# source_wifi_rev_a.net
KiCad netlist of a schematic drawn in EAGLE
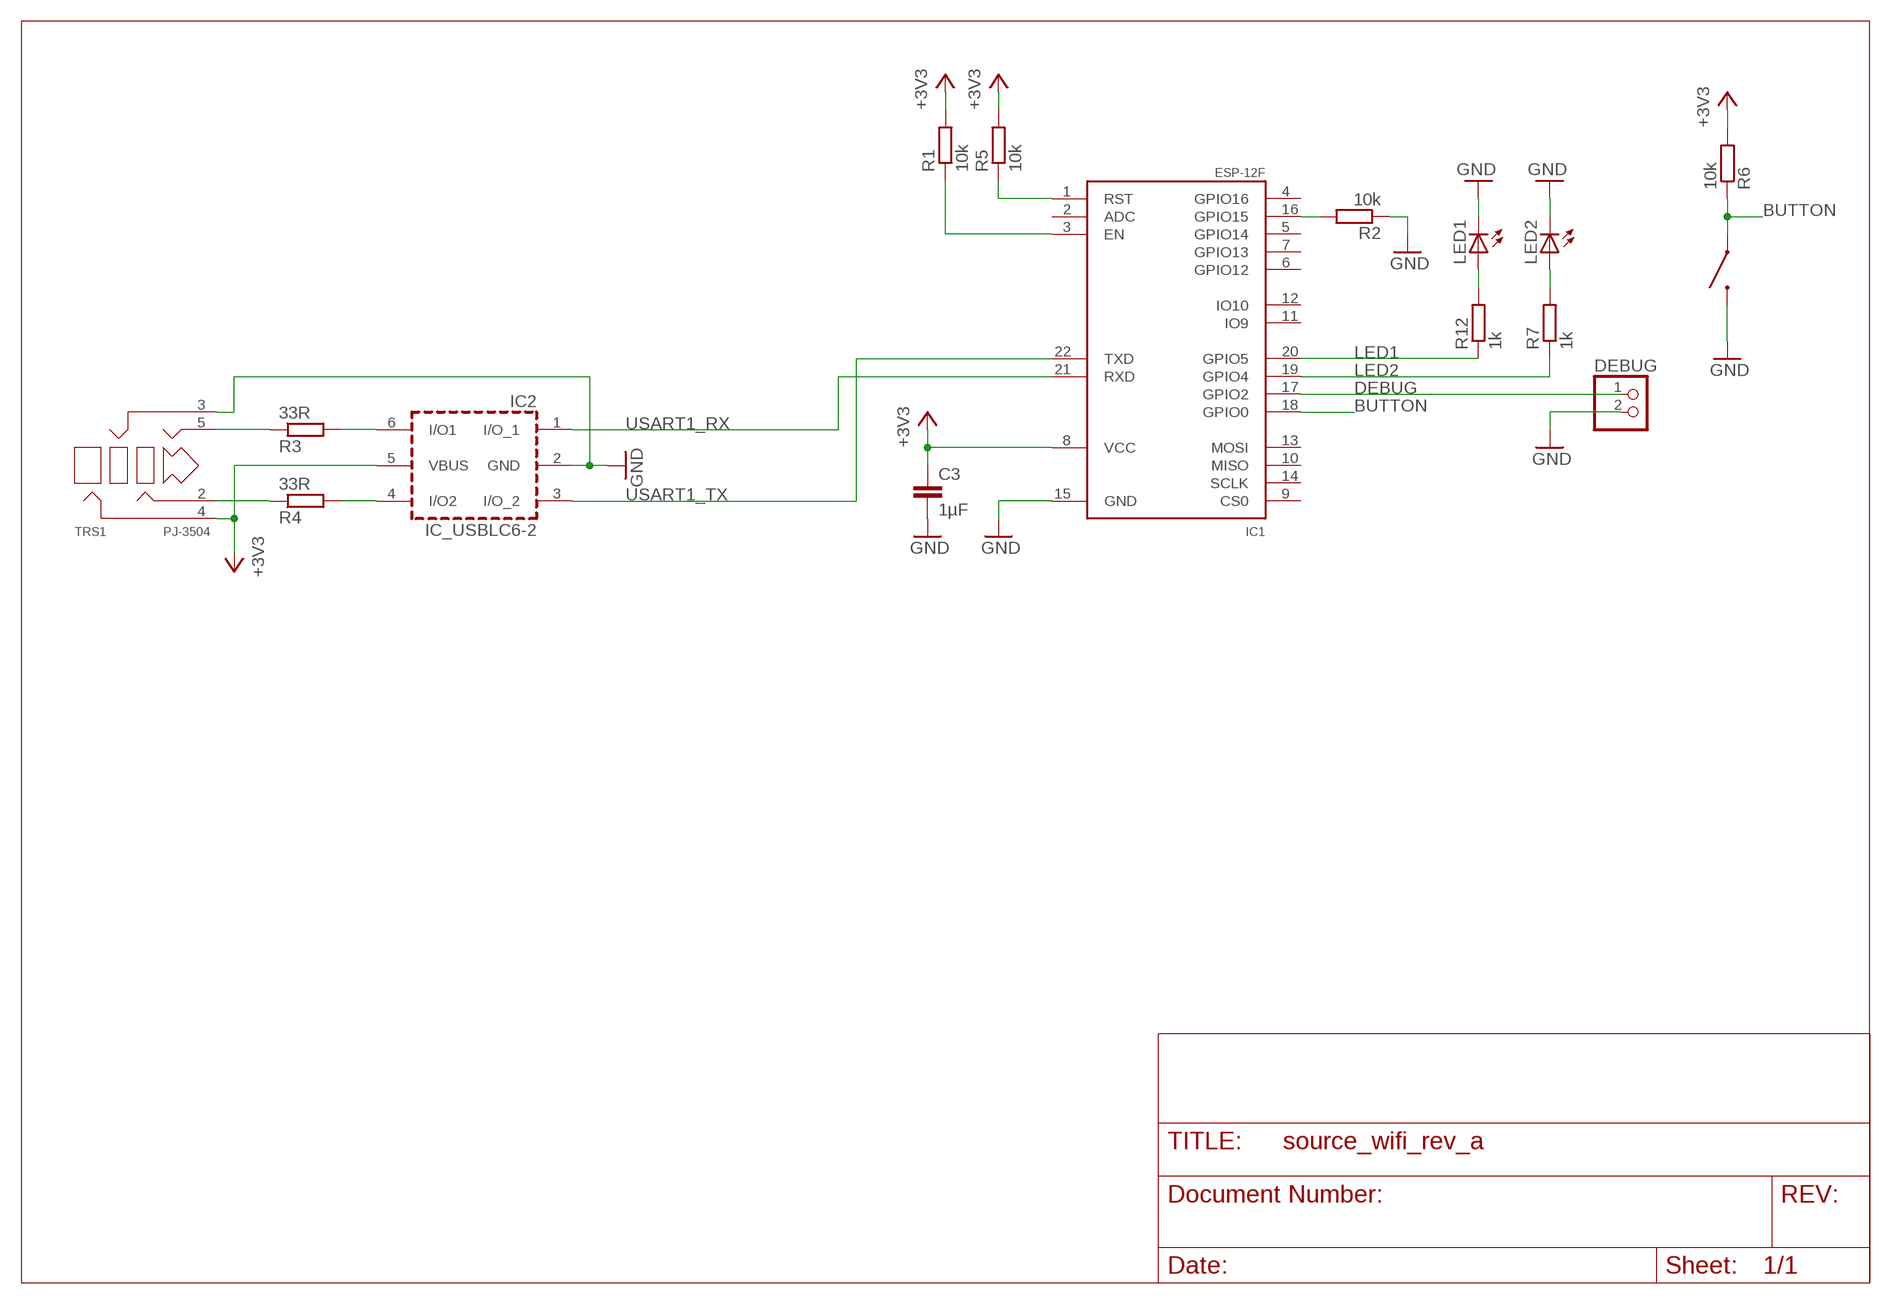
[diagram p0: schematic, sheet 1]

(export (version "E")
  (design (tool "Eeschema 10.0.6"))
  (components
    (comp (ref "C3")
      (value "1µF")
      (footprint "eagle-import:C0603")
      (libsource (lib "eagle-import") (part "C-EUC0603"))
    )
    (comp (ref "DEBUG")
      (value "HEADER-1X2ROUND")
      (footprint "eagle-import:1X02_ROUND")
      (libsource (lib "eagle-import") (part "HEADER-1X2ROUND"))
    )
    (comp (ref "IC1")
      (value "ESP-12F")
      (footprint "eagle-import:ESP-12F")
      (libsource (lib "eagle-import") (part "ESP-12F"))
    )
    (comp (ref "IC2")
      (value "IC_USBLC6-2")
      (footprint "eagle-import:SOT-23-6L")
      (libsource (lib "eagle-import") (part "IC_USBLC6-2"))
    )
    (comp (ref "ISP")
      (value "TACT-SWITCH-40-40")
      (footprint "eagle-import:40-40")
      (libsource (lib "eagle-import") (part "TACT-SWITCH-40-40"))
    )
    (comp (ref "LED1")
      (value "LEDCHIP-LED0603")
      (footprint "eagle-import:CHIP-LED0603")
      (libsource (lib "eagle-import") (part "LEDCHIP-LED0603"))
    )
    (comp (ref "LED2")
      (value "LEDCHIP-LED0603")
      (footprint "eagle-import:CHIP-LED0603")
      (libsource (lib "eagle-import") (part "LEDCHIP-LED0603"))
    )
    (comp (ref "R1")
      (value "10k")
      (footprint "eagle-import:R0603")
      (libsource (lib "eagle-import") (part "R-EU_R0603"))
    )
    (comp (ref "R2")
      (value "10k")
      (footprint "eagle-import:R0603")
      (libsource (lib "eagle-import") (part "R-EU_R0603"))
    )
    (comp (ref "R3")
      (value "33R")
      (footprint "eagle-import:R0603")
      (libsource (lib "eagle-import") (part "R-EU_R0603"))
    )
    (comp (ref "R4")
      (value "33R")
      (footprint "eagle-import:R0603")
      (libsource (lib "eagle-import") (part "R-EU_R0603"))
    )
    (comp (ref "R5")
      (value "10k")
      (footprint "eagle-import:R0603")
      (libsource (lib "eagle-import") (part "R-EU_R0603"))
    )
    (comp (ref "R6")
      (value "10k")
      (footprint "eagle-import:R0603")
      (libsource (lib "eagle-import") (part "R-EU_R0603"))
    )
    (comp (ref "R7")
      (value "1k")
      (footprint "eagle-import:R0603")
      (libsource (lib "eagle-import") (part "R-EU_R0603"))
    )
    (comp (ref "R12")
      (value "1k")
      (footprint "eagle-import:R0603")
      (libsource (lib "eagle-import") (part "R-EU_R0603"))
    )
    (comp (ref "TRS1")
      (value "PJ-3504")
      (footprint "eagle-import:YD-PJ-3504")
      (libsource (lib "eagle-import") (part "PJ-3504"))
    )
  )
  (nets
    (net (code "1") (name "+3V3") (class "Default")
      (node (ref "C3") (pin "1") (pinfunction "1_1") (pintype "passive"))
      (node (ref "IC1") (pin "8") (pinfunction "VCC_8") (pintype "bidirectional"))
      (node (ref "IC2") (pin "5") (pinfunction "VBUS_5") (pintype "bidirectional"))
      (node (ref "R1") (pin "2") (pinfunction "2_2") (pintype "passive"))
      (node (ref "R5") (pin "2") (pinfunction "2_2") (pintype "passive"))
      (node (ref "R6") (pin "2") (pinfunction "2_2") (pintype "passive"))
      (node (ref "TRS1") (pin "4") (pinfunction "4_4") (pintype "bidirectional"))
    )
    (net (code "2") (name "/BUTTON") (class "Default")
      (node (ref "IC1") (pin "18") (pinfunction "GPIO0_18") (pintype "bidirectional"))
      (node (ref "ISP") (pin "3") (pinfunction "P$2_3") (pintype "bidirectional"))
      (node (ref "ISP") (pin "4") (pinfunction "P$2_4") (pintype "bidirectional"))
      (node (ref "R6") (pin "1") (pinfunction "1_1") (pintype "passive"))
    )
    (net (code "3") (name "/DEBUG") (class "Default")
      (node (ref "DEBUG") (pin "1") (pinfunction "1_1") (pintype "passive"))
      (node (ref "IC1") (pin "17") (pinfunction "GPIO2_17") (pintype "bidirectional"))
    )
    (net (code "4") (name "/LED1") (class "Default")
      (node (ref "IC1") (pin "20") (pinfunction "GPIO5_20") (pintype "bidirectional"))
      (node (ref "R12") (pin "1") (pinfunction "1_1") (pintype "passive"))
    )
    (net (code "5") (name "/LED2") (class "Default")
      (node (ref "IC1") (pin "19") (pinfunction "GPIO4_19") (pintype "bidirectional"))
      (node (ref "R7") (pin "1") (pinfunction "1_1") (pintype "passive"))
    )
    (net (code "6") (name "/USART1_RX") (class "Default")
      (node (ref "IC1") (pin "21") (pinfunction "RXD_21") (pintype "bidirectional"))
      (node (ref "IC2") (pin "1") (pinfunction "I/O_1_1") (pintype "bidirectional"))
    )
    (net (code "7") (name "/USART1_TX") (class "Default")
      (node (ref "IC1") (pin "22") (pinfunction "TXD_22") (pintype "bidirectional"))
      (node (ref "IC2") (pin "3") (pinfunction "I/O_2_3") (pintype "bidirectional"))
    )
    (net (code "8") (name "GND") (class "Default")
      (node (ref "C3") (pin "2") (pinfunction "2_2") (pintype "passive"))
      (node (ref "DEBUG") (pin "2") (pinfunction "2_2") (pintype "passive"))
      (node (ref "IC1") (pin "15") (pinfunction "GND_15") (pintype "bidirectional"))
      (node (ref "IC2") (pin "2") (pinfunction "GND_2") (pintype "bidirectional"))
      (node (ref "ISP") (pin "1") (pinfunction "P$1_1") (pintype "bidirectional"))
      (node (ref "ISP") (pin "2") (pinfunction "P$1_2") (pintype "bidirectional"))
      (node (ref "LED1") (pin "C") (pinfunction "C_C") (pintype "passive"))
      (node (ref "LED2") (pin "C") (pinfunction "C_C") (pintype "passive"))
      (node (ref "R2") (pin "1") (pinfunction "1_1") (pintype "passive"))
      (node (ref "TRS1") (pin "3") (pinfunction "3_3") (pintype "bidirectional"))
    )
    (net (code "9") (name "Net-(IC1-EN)") (class "Default")
      (node (ref "IC1") (pin "3") (pinfunction "EN_3") (pintype "bidirectional"))
      (node (ref "R1") (pin "1") (pinfunction "1_1") (pintype "passive"))
    )
    (net (code "10") (name "Net-(IC1-GPIO15)") (class "Default")
      (node (ref "IC1") (pin "16") (pinfunction "GPIO15_16") (pintype "bidirectional"))
      (node (ref "R2") (pin "2") (pinfunction "2_2") (pintype "passive"))
    )
    (net (code "11") (name "Net-(IC1-RST)") (class "Default")
      (node (ref "IC1") (pin "1") (pinfunction "RST_1") (pintype "bidirectional"))
      (node (ref "R5") (pin "1") (pinfunction "1_1") (pintype "passive"))
    )
    (net (code "12") (name "Net-(IC2-I{slash}O1)") (class "Default")
      (node (ref "IC2") (pin "6") (pinfunction "I/O1_6") (pintype "bidirectional"))
      (node (ref "R3") (pin "2") (pinfunction "2_2") (pintype "passive"))
    )
    (net (code "13") (name "Net-(IC2-I{slash}O2)") (class "Default")
      (node (ref "IC2") (pin "4") (pinfunction "I/O2_4") (pintype "bidirectional"))
      (node (ref "R4") (pin "2") (pinfunction "2_2") (pintype "passive"))
    )
    (net (code "14") (name "Net-(LED1-PadA)") (class "Default")
      (node (ref "LED1") (pin "A") (pinfunction "A_A") (pintype "passive"))
      (node (ref "R12") (pin "2") (pinfunction "2_2") (pintype "passive"))
    )
    (net (code "15") (name "Net-(LED2-PadA)") (class "Default")
      (node (ref "LED2") (pin "A") (pinfunction "A_A") (pintype "passive"))
      (node (ref "R7") (pin "2") (pinfunction "2_2") (pintype "passive"))
    )
    (net (code "16") (name "Net-(R3-Pad1)") (class "Default")
      (node (ref "R3") (pin "1") (pinfunction "1_1") (pintype "passive"))
      (node (ref "TRS1") (pin "5") (pinfunction "5_5") (pintype "bidirectional"))
    )
    (net (code "17") (name "Net-(R4-Pad1)") (class "Default")
      (node (ref "R4") (pin "1") (pinfunction "1_1") (pintype "passive"))
      (node (ref "TRS1") (pin "2") (pinfunction "2_2") (pintype "bidirectional"))
    )
    (net (code "18") (name "unconnected-(IC1-ADC-Pad2)") (class "Default")
      (node (ref "IC1") (pin "2") (pinfunction "ADC_2") (pintype "bidirectional"))
    )
    (net (code "19") (name "unconnected-(IC1-CS0-Pad9)") (class "Default")
      (node (ref "IC1") (pin "9") (pinfunction "CS0_9") (pintype "bidirectional"))
    )
    (net (code "20") (name "unconnected-(IC1-GPIO12-Pad6)") (class "Default")
      (node (ref "IC1") (pin "6") (pinfunction "GPIO12_6") (pintype "bidirectional"))
    )
    (net (code "21") (name "unconnected-(IC1-GPIO13-Pad7)") (class "Default")
      (node (ref "IC1") (pin "7") (pinfunction "GPIO13_7") (pintype "bidirectional"))
    )
    (net (code "22") (name "unconnected-(IC1-GPIO14-Pad5)") (class "Default")
      (node (ref "IC1") (pin "5") (pinfunction "GPIO14_5") (pintype "bidirectional"))
    )
    (net (code "23") (name "unconnected-(IC1-GPIO16-Pad4)") (class "Default")
      (node (ref "IC1") (pin "4") (pinfunction "GPIO16_4") (pintype "bidirectional"))
    )
    (net (code "24") (name "unconnected-(IC1-IO9-Pad11)") (class "Default")
      (node (ref "IC1") (pin "11") (pinfunction "IO9_11") (pintype "bidirectional"))
    )
    (net (code "25") (name "unconnected-(IC1-IO10-Pad12)") (class "Default")
      (node (ref "IC1") (pin "12") (pinfunction "IO10_12") (pintype "bidirectional"))
    )
    (net (code "26") (name "unconnected-(IC1-MISO-Pad10)") (class "Default")
      (node (ref "IC1") (pin "10") (pinfunction "MISO_10") (pintype "bidirectional"))
    )
    (net (code "27") (name "unconnected-(IC1-MOSI-Pad13)") (class "Default")
      (node (ref "IC1") (pin "13") (pinfunction "MOSI_13") (pintype "bidirectional"))
    )
    (net (code "28") (name "unconnected-(IC1-SCLK-Pad14)") (class "Default")
      (node (ref "IC1") (pin "14") (pinfunction "SCLK_14") (pintype "bidirectional"))
    )
  )
)
